# TCXOBreakout.net
KiCad netlist of a schematic drawn in EAGLE
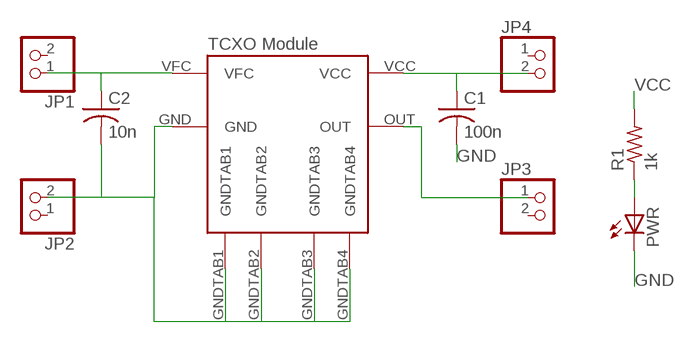
[diagram p0: schematic, sheet 1]

(export (version "E")
  (design (tool "Eeschema 10.0.6"))
  (components
    (comp (ref "C1")
      (value "100n")
      (footprint "eagle-import:C0603")
      (libsource (lib "eagle-import") (part "C-USC0603"))
    )
    (comp (ref "C2")
      (value "10n")
      (footprint "eagle-import:C0603")
      (libsource (lib "eagle-import") (part "C-USC0603"))
    )
    (comp (ref "JP1")
      (value "PINHD-1X2")
      (footprint "eagle-import:1X02")
      (libsource (lib "eagle-import") (part "PINHD-1X2"))
    )
    (comp (ref "JP2")
      (value "PINHD-1X2")
      (footprint "eagle-import:1X02")
      (libsource (lib "eagle-import") (part "PINHD-1X2"))
    )
    (comp (ref "JP3")
      (value "PINHD-1X2")
      (footprint "eagle-import:1X02")
      (libsource (lib "eagle-import") (part "PINHD-1X2"))
    )
    (comp (ref "JP4")
      (value "PINHD-1X2")
      (footprint "eagle-import:1X02")
      (libsource (lib "eagle-import") (part "PINHD-1X2"))
    )
    (comp (ref "PWR")
      (value "LEDCHIPLED_0805")
      (footprint "eagle-import:CHIPLED_0805")
      (libsource (lib "eagle-import") (part "LEDCHIPLED_0805"))
    )
    (comp (ref "R1")
      (value "1k")
      (footprint "eagle-import:R0603")
      (libsource (lib "eagle-import") (part "R-US_R0603"))
    )
    (comp (ref "U$1")
      (value "TCXO2")
      (footprint "eagle-import:TCXO2")
      (libsource (lib "eagle-import") (part "TCXO2"))
    )
  )
  (nets
    (net (code "1") (name "/GND") (class "Default")
      (node (ref "C1") (pin "2") (pinfunction "2_2") (pintype "passive"))
      (node (ref "C2") (pin "2") (pinfunction "2_2") (pintype "passive"))
      (node (ref "JP2") (pin "2") (pinfunction "2_2") (pintype "passive"))
      (node (ref "PWR") (pin "C") (pinfunction "C_C") (pintype "passive"))
      (node (ref "U$1") (pin "GND") (pinfunction "GND_GND") (pintype "bidirectional"))
      (node (ref "U$1") (pin "GNDTAB1") (pinfunction "GNDTAB1_GNDTAB1") (pintype "bidirectional"))
      (node (ref "U$1") (pin "GNDTAB2") (pinfunction "GNDTAB2_GNDTAB2") (pintype "bidirectional"))
      (node (ref "U$1") (pin "GNDTAB3") (pinfunction "GNDTAB3_GNDTAB3") (pintype "bidirectional"))
      (node (ref "U$1") (pin "GNDTAB4") (pinfunction "GNDTAB4_GNDTAB4") (pintype "bidirectional"))
    )
    (net (code "2") (name "/VCC") (class "Default")
      (node (ref "C1") (pin "1") (pinfunction "1_1") (pintype "passive"))
      (node (ref "JP4") (pin "2") (pinfunction "2_2") (pintype "passive"))
      (node (ref "R1") (pin "2") (pinfunction "2_2") (pintype "passive"))
      (node (ref "U$1") (pin "VCC") (pinfunction "VCC_VCC") (pintype "bidirectional"))
    )
    (net (code "3") (name "Net-(C2-Pad1)") (class "Default")
      (node (ref "C2") (pin "1") (pinfunction "1_1") (pintype "passive"))
      (node (ref "JP1") (pin "1") (pinfunction "1_1") (pintype "passive"))
      (node (ref "U$1") (pin "VFC") (pinfunction "VFC_VFC") (pintype "bidirectional"))
    )
    (net (code "4") (name "Net-(JP3-Pad1)") (class "Default")
      (node (ref "JP3") (pin "1") (pinfunction "1_1") (pintype "passive"))
      (node (ref "U$1") (pin "OUT") (pinfunction "OUT_OUT") (pintype "bidirectional"))
    )
    (net (code "5") (name "Net-(PWR-PadA)") (class "Default")
      (node (ref "PWR") (pin "A") (pinfunction "A_A") (pintype "passive"))
      (node (ref "R1") (pin "1") (pinfunction "1_1") (pintype "passive"))
    )
    (net (code "6") (name "unconnected-(JP1-Pad2)") (class "Default")
      (node (ref "JP1") (pin "2") (pinfunction "2_2") (pintype "passive"))
    )
    (net (code "7") (name "unconnected-(JP2-Pad1)") (class "Default")
      (node (ref "JP2") (pin "1") (pinfunction "1_1") (pintype "passive"))
    )
    (net (code "8") (name "unconnected-(JP3-Pad2)") (class "Default")
      (node (ref "JP3") (pin "2") (pinfunction "2_2") (pintype "passive"))
    )
    (net (code "9") (name "unconnected-(JP4-Pad1)") (class "Default")
      (node (ref "JP4") (pin "1") (pinfunction "1_1") (pintype "passive"))
    )
  )
)
